# TELM0002ADC.net
KiCad netlist of a schematic drawn in Altium Designer
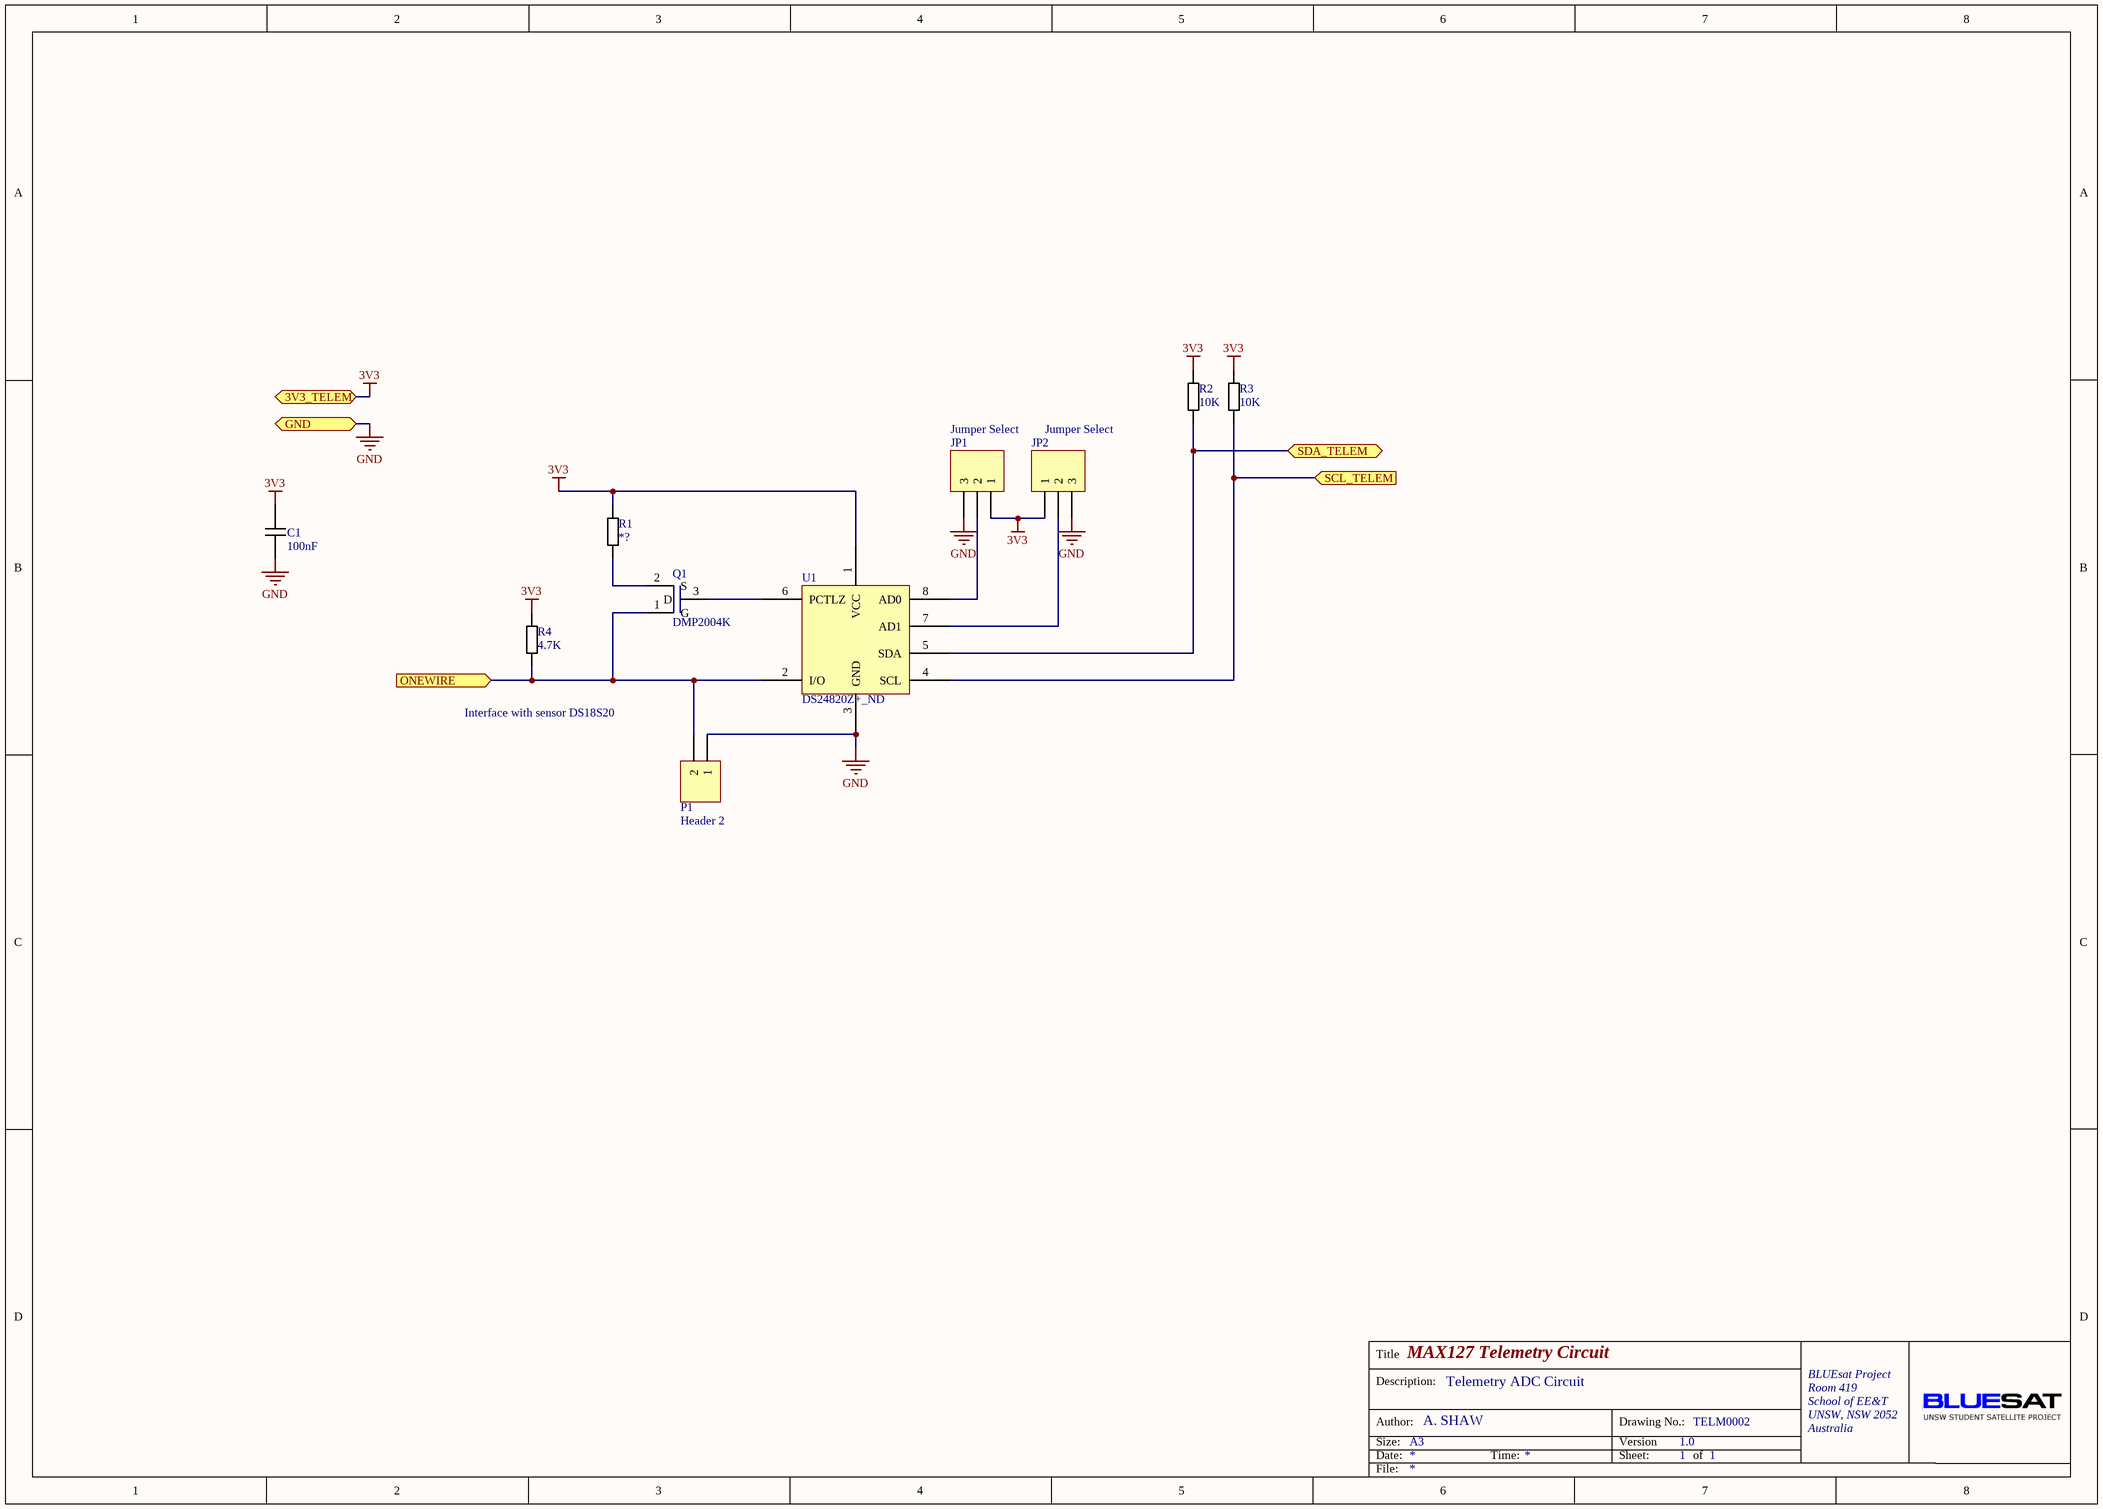
[diagram p0: TELM0002ADC.SchDoc]

(export (version "E")
  (design (tool "Eeschema 10.0.6"))
  (components
    (comp (ref "C1")
      (value "100nF")
      (footprint "0805 Cap")
      (description "0805 MLCC - X7R, 10%")
      (fields (field (name "Comment") "0805 Cap"))
      (libsource (lib "Schlib1") (part "0805 MLCC - X7R, 10%"))
    )
    (comp (ref "JP1")
      (value "Jumper Select")
      (footprint "SOLDER_JUMPER_3_A")
      (description "Header, 3-Pin")
      (fields (field (name "PUBLISHER") "Altium Limited"))
      (libsource (lib "Miscellaneous Connectors") (part "Header 3"))
    )
    (comp (ref "JP2")
      (value "Jumper Select")
      (footprint "SOLDER_JUMPER_3_A")
      (description "Header, 3-Pin")
      (fields (field (name "PUBLISHER") "Altium Limited"))
      (libsource (lib "") (part "Header 3_1"))
    )
    (comp (ref "P1")
      (value "Header 2")
      (footprint "HDR1X2")
      (description "Header, 2-Pin")
      (fields (field (name "PUBLISHER") "Altium Limited"))
      (libsource (lib "Miscellaneous Connectors") (part "Header 2"))
    )
    (comp (ref "Q1")
      (value "DMP2004K")
      (footprint "DMP2004KDITR-ND")
      (description "MOSFET P-CH 20V 600MA SOT23-3")
      (libsource (lib "Telemetry") (part "DMP2004K"))
    )
    (comp (ref "R1")
      (value "*?")
      (footprint "0805 Resistor")
      (description "0805 Thick Film Resistor 1%")
      (fields (field (name "Comment") "0805 Resistor"))
      (libsource (lib "Schlib1") (part "0805 Thick Film Resistor 1%"))
    )
    (comp (ref "R2")
      (value "10K")
      (footprint "0805 Resistor")
      (description "0805 Thick Film Resistor 1%")
      (fields (field (name "Comment") "0805 Resistor"))
      (libsource (lib "Schlib1") (part "0805 Thick Film Resistor 1%"))
    )
    (comp (ref "R3")
      (value "10K")
      (footprint "0805 Resistor")
      (description "0805 Thick Film Resistor 1%")
      (fields (field (name "Comment") "0805 Resistor"))
      (libsource (lib "Schlib1") (part "0805 Thick Film Resistor 1%"))
    )
    (comp (ref "R4")
      (value "4.7K")
      (footprint "0805 Resistor")
      (description "0603 Thick Film Resistor 1%")
      (fields (field (name "Comment") "0603 Resistor"))
      (libsource (lib "Schlib1") (part "0603 Thick Film Resistor 1%"))
    )
    (comp (ref "U1")
      (value "DS24820Z+_ND")
      (footprint "DS2482-100")
      (libsource (lib "Telemetry") (part "DS24820Z+_ND"))
    )
  )
  (nets
    (net (code "1") (name "/ONEWIRE") (class "Default")
      (node (ref "P1") (pin "2") (pinfunction "2_2") (pintype "passive"))
      (node (ref "Q1") (pin "1") (pinfunction "G_1") (pintype "passive"))
      (node (ref "R4") (pin "1") (pinfunction "1_1") (pintype "passive"))
      (node (ref "U1") (pin "2") (pinfunction "I/O_2") (pintype "passive"))
    )
    (net (code "2") (name "/SCL_TELEM") (class "Default")
      (node (ref "R3") (pin "1") (pinfunction "1_1") (pintype "passive"))
      (node (ref "U1") (pin "4") (pinfunction "SCL_4") (pintype "passive"))
    )
    (net (code "3") (name "/SDA_TELEM") (class "Default")
      (node (ref "R2") (pin "1") (pinfunction "1_1") (pintype "passive"))
      (node (ref "U1") (pin "5") (pinfunction "SDA_5") (pintype "passive"))
    )
    (net (code "4") (name "3V3") (class "Default")
      (node (ref "C1") (pin "2") (pinfunction "2_2") (pintype "passive"))
      (node (ref "JP1") (pin "1") (pinfunction "1_1") (pintype "passive"))
      (node (ref "JP2") (pin "1") (pinfunction "1_1") (pintype "passive"))
      (node (ref "R1") (pin "2") (pinfunction "2_2") (pintype "passive"))
      (node (ref "R2") (pin "2") (pinfunction "2_2") (pintype "passive"))
      (node (ref "R3") (pin "2") (pinfunction "2_2") (pintype "passive"))
      (node (ref "R4") (pin "2") (pinfunction "2_2") (pintype "passive"))
      (node (ref "U1") (pin "1") (pinfunction "VCC_1") (pintype "passive"))
    )
    (net (code "5") (name "GND") (class "Default")
      (node (ref "C1") (pin "1") (pinfunction "1_1") (pintype "passive"))
      (node (ref "JP1") (pin "3") (pinfunction "3_3") (pintype "passive"))
      (node (ref "JP2") (pin "3") (pinfunction "3_3") (pintype "passive"))
      (node (ref "P1") (pin "1") (pinfunction "1_1") (pintype "passive"))
      (node (ref "U1") (pin "3") (pinfunction "GND_3") (pintype "passive"))
    )
    (net (code "6") (name "Net-(Q1-D)") (class "Default")
      (node (ref "Q1") (pin "3") (pinfunction "D_3") (pintype "passive"))
      (node (ref "U1") (pin "6") (pinfunction "PCTLZ_6") (pintype "passive"))
    )
    (net (code "7") (name "Net-(Q1-S)") (class "Default")
      (node (ref "Q1") (pin "2") (pinfunction "S_2") (pintype "passive"))
      (node (ref "R1") (pin "1") (pinfunction "1_1") (pintype "passive"))
    )
    (net (code "8") (name "Net-(U1-AD0)") (class "Default")
      (node (ref "JP1") (pin "2") (pinfunction "2_2") (pintype "passive"))
      (node (ref "U1") (pin "8") (pinfunction "AD0_8") (pintype "passive"))
    )
    (net (code "9") (name "Net-(U1-AD1)") (class "Default")
      (node (ref "JP2") (pin "2") (pinfunction "2_2") (pintype "passive"))
      (node (ref "U1") (pin "7") (pinfunction "AD1_7") (pintype "passive"))
    )
  )
)
